# Board.net
KiCad netlist of a schematic drawn in EAGLE
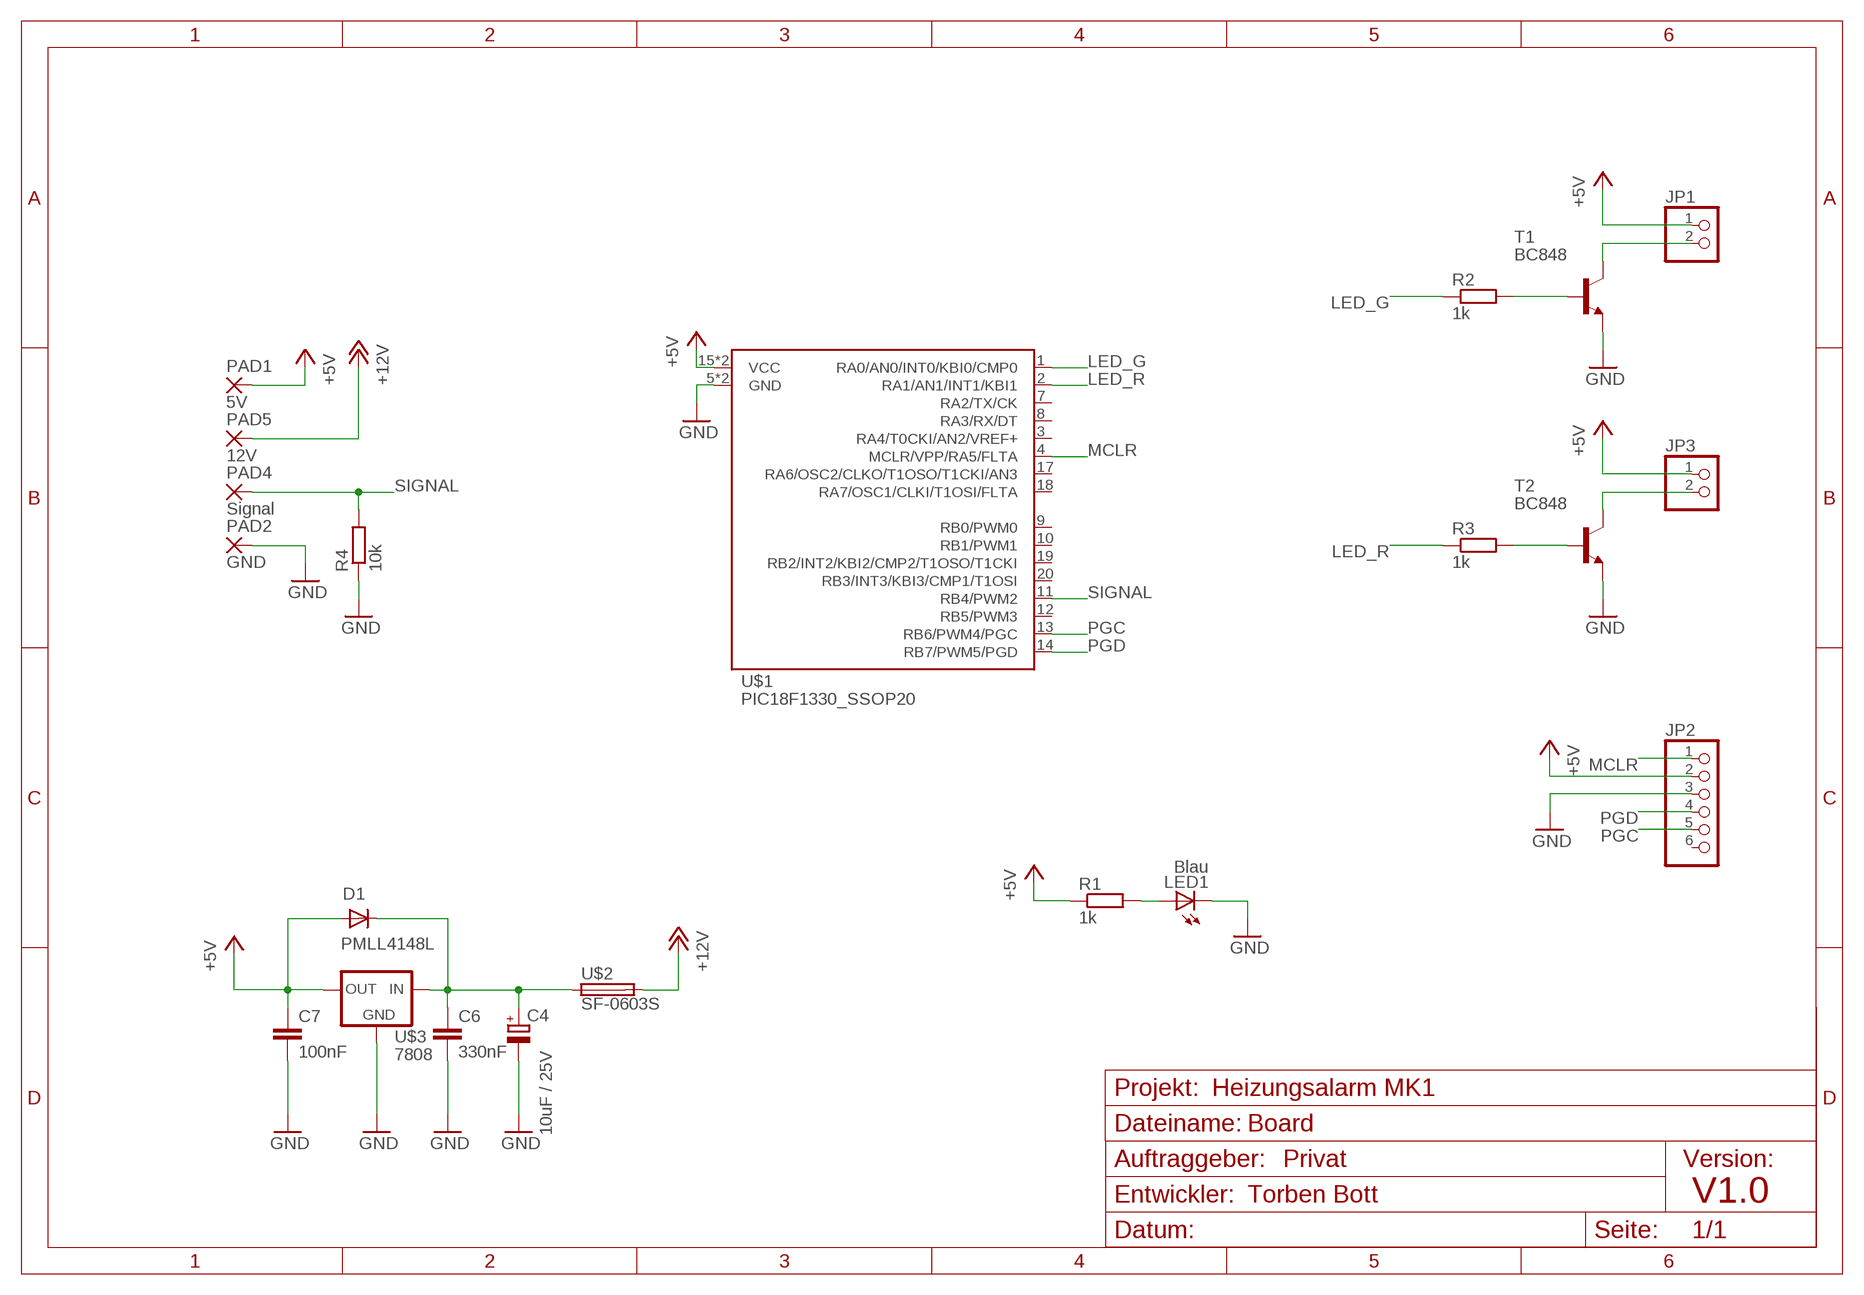
[diagram p0: schematic, sheet 1]

(export (version "E")
  (design (tool "Eeschema 10.0.6"))
  (components
    (comp (ref "C4")
      (value "10uF / 25V")
      (footprint "eagle-import:D_7343-31R")
      (libsource (lib "eagle-import") (part "CPOL-EUD/7343-31R"))
    )
    (comp (ref "C6")
      (value "330nF")
      (footprint "eagle-import:C0805")
      (libsource (lib "eagle-import") (part "C-EUC0805"))
    )
    (comp (ref "C7")
      (value "100nF")
      (footprint "eagle-import:C0805")
      (libsource (lib "eagle-import") (part "C-EUC0805"))
    )
    (comp (ref "D1")
      (value "PMLL4148L")
      (footprint "eagle-import:SOD80C")
      (libsource (lib "eagle-import") (part "PMLL4148L"))
    )
    (comp (ref "JP1")
      (value "PINHD-1X2/90")
      (footprint "eagle-import:1X02_90")
      (libsource (lib "eagle-import") (part "PINHD-1X2/90"))
    )
    (comp (ref "JP2")
      (value "PINHD-1X6")
      (footprint "eagle-import:1X06")
      (libsource (lib "eagle-import") (part "PINHD-1X6"))
    )
    (comp (ref "JP3")
      (value "PINHD-1X2/90")
      (footprint "eagle-import:1X02_90")
      (libsource (lib "eagle-import") (part "PINHD-1X2/90"))
    )
    (comp (ref "LED1")
      (value "Blau")
      (footprint "eagle-import:CHIP-LED0805")
      (libsource (lib "eagle-import") (part "LEDCHIP-LED0805"))
    )
    (comp (ref "PAD1")
      (value "5V")
      (footprint "eagle-import:5-1,8")
      (libsource (lib "eagle-import") (part "WIREPADSMD5-1,8"))
    )
    (comp (ref "PAD2")
      (value "GND")
      (footprint "eagle-import:5-1,8")
      (libsource (lib "eagle-import") (part "WIREPADSMD5-1,8"))
    )
    (comp (ref "PAD4")
      (value "Signal")
      (footprint "eagle-import:5-1,8")
      (libsource (lib "eagle-import") (part "WIREPADSMD5-1,8"))
    )
    (comp (ref "PAD5")
      (value "12V")
      (footprint "eagle-import:5-1,8")
      (libsource (lib "eagle-import") (part "WIREPADSMD5-1,8"))
    )
    (comp (ref "R1")
      (value "1k")
      (footprint "eagle-import:R0805")
      (libsource (lib "eagle-import") (part "R-EU_R0805"))
    )
    (comp (ref "R2")
      (value "1k")
      (footprint "eagle-import:R0805")
      (libsource (lib "eagle-import") (part "R-EU_R0805"))
    )
    (comp (ref "R3")
      (value "1k")
      (footprint "eagle-import:R0805")
      (libsource (lib "eagle-import") (part "R-EU_R0805"))
    )
    (comp (ref "R4")
      (value "10k")
      (footprint "eagle-import:R0805")
      (libsource (lib "eagle-import") (part "R-EU_R0805"))
    )
    (comp (ref "T1")
      (value "BC848")
      (footprint "eagle-import:SOT23")
      (libsource (lib "eagle-import") (part "BC848"))
    )
    (comp (ref "T2")
      (value "BC848")
      (footprint "eagle-import:SOT23")
      (libsource (lib "eagle-import") (part "BC848"))
    )
    (comp (ref "U$1")
      (value "PIC18F1330_SSOP20")
      (footprint "eagle-import:SSOP20")
      (libsource (lib "eagle-import") (part "PIC18F1330_SSOP20"))
    )
    (comp (ref "U$2")
      (value "SF-0603S")
      (footprint "eagle-import:R0603")
      (libsource (lib "eagle-import") (part "SF-0603S"))
    )
    (comp (ref "U$3")
      (value "7808")
      (footprint "eagle-import:SOT89")
      (libsource (lib "eagle-import") (part "78XX_(SOT89)"))
    )
  )
  (nets
    (net (code "1") (name "+5V") (class "Default")
      (node (ref "C7") (pin "1") (pinfunction "1_1") (pintype "passive"))
      (node (ref "D1") (pin "2") (pinfunction "A_2") (pintype "passive"))
      (node (ref "JP1") (pin "1") (pinfunction "1_1") (pintype "passive"))
      (node (ref "JP2") (pin "2") (pinfunction "2_2") (pintype "passive"))
      (node (ref "JP3") (pin "1") (pinfunction "1_1") (pintype "passive"))
      (node (ref "PAD1") (pin "1") (pinfunction "P_1") (pintype "passive"))
      (node (ref "R1") (pin "1") (pinfunction "1_1") (pintype "passive"))
      (node (ref "U$1") (pin "15") (pinfunction "VCC_15") (pintype "bidirectional"))
      (node (ref "U$1") (pin "16") (pinfunction "VCC_16") (pintype "bidirectional"))
      (node (ref "U$3") (pin "1") (pinfunction "IN_1") (pintype "input"))
    )
    (net (code "2") (name "+12V") (class "Default")
      (node (ref "PAD5") (pin "1") (pinfunction "P_1") (pintype "passive"))
      (node (ref "U$2") (pin "2") (pinfunction "2_2") (pintype "passive"))
    )
    (net (code "3") (name "/LED_G") (class "Default")
      (node (ref "R2") (pin "1") (pinfunction "1_1") (pintype "passive"))
      (node (ref "U$1") (pin "1") (pinfunction "RA0/AN0/INT0/KBI0/CMP0_1") (pintype "bidirectional"))
    )
    (net (code "4") (name "/LED_R") (class "Default")
      (node (ref "R3") (pin "1") (pinfunction "1_1") (pintype "passive"))
      (node (ref "U$1") (pin "2") (pinfunction "RA1/AN1/INT1/KBI1_2") (pintype "bidirectional"))
    )
    (net (code "5") (name "/MCLR") (class "Default")
      (node (ref "JP2") (pin "1") (pinfunction "1_1") (pintype "passive"))
      (node (ref "U$1") (pin "4") (pinfunction "MCLR/VPP/RA5/FLTA_4") (pintype "bidirectional"))
    )
    (net (code "6") (name "/PGC") (class "Default")
      (node (ref "JP2") (pin "5") (pinfunction "5_5") (pintype "passive"))
      (node (ref "U$1") (pin "13") (pinfunction "RB6/PWM4/PGC_13") (pintype "bidirectional"))
    )
    (net (code "7") (name "/PGD") (class "Default")
      (node (ref "JP2") (pin "4") (pinfunction "4_4") (pintype "passive"))
      (node (ref "U$1") (pin "14") (pinfunction "RB7/PWM5/PGD_14") (pintype "bidirectional"))
    )
    (net (code "8") (name "/SIGNAL") (class "Default")
      (node (ref "PAD4") (pin "1") (pinfunction "P_1") (pintype "passive"))
      (node (ref "R4") (pin "2") (pinfunction "2_2") (pintype "passive"))
      (node (ref "U$1") (pin "11") (pinfunction "RB4/PWM2_11") (pintype "bidirectional"))
    )
    (net (code "9") (name "GND") (class "Default")
      (node (ref "C4") (pin "-") (pinfunction "-_-") (pintype "passive"))
      (node (ref "C6") (pin "2") (pinfunction "2_2") (pintype "passive"))
      (node (ref "C7") (pin "2") (pinfunction "2_2") (pintype "passive"))
      (node (ref "JP2") (pin "3") (pinfunction "3_3") (pintype "passive"))
      (node (ref "LED1") (pin "C") (pinfunction "C_C") (pintype "passive"))
      (node (ref "PAD2") (pin "1") (pinfunction "P_1") (pintype "passive"))
      (node (ref "R4") (pin "1") (pinfunction "1_1") (pintype "passive"))
      (node (ref "T1") (pin "2") (pinfunction "E_2") (pintype "passive"))
      (node (ref "T2") (pin "2") (pinfunction "E_2") (pintype "passive"))
      (node (ref "U$1") (pin "5") (pinfunction "GND_5") (pintype "bidirectional"))
      (node (ref "U$1") (pin "6") (pinfunction "GND_6") (pintype "bidirectional"))
      (node (ref "U$3") (pin "2") (pinfunction "GND_2") (pintype "input"))
      (node (ref "U$3") (pin "2@1") (pinfunction "GND_2@1") (pintype "input"))
    )
    (net (code "10") (name "Net-(D1-K)") (class "Default")
      (node (ref "C4") (pin "+") (pinfunction "+_+") (pintype "passive"))
      (node (ref "C6") (pin "1") (pinfunction "1_1") (pintype "passive"))
      (node (ref "D1") (pin "1") (pinfunction "K_1") (pintype "passive"))
      (node (ref "U$2") (pin "1") (pinfunction "1_1") (pintype "passive"))
      (node (ref "U$3") (pin "3") (pinfunction "OUT_3") (pintype "passive"))
    )
    (net (code "11") (name "Net-(LED1-PadA)") (class "Default")
      (node (ref "LED1") (pin "A") (pinfunction "A_A") (pintype "passive"))
      (node (ref "R1") (pin "2") (pinfunction "2_2") (pintype "passive"))
    )
    (net (code "12") (name "Net-(T1-B)") (class "Default")
      (node (ref "R2") (pin "2") (pinfunction "2_2") (pintype "passive"))
      (node (ref "T1") (pin "1") (pinfunction "B_1") (pintype "passive"))
    )
    (net (code "13") (name "Net-(T1-C)") (class "Default")
      (node (ref "JP1") (pin "2") (pinfunction "2_2") (pintype "passive"))
      (node (ref "T1") (pin "3") (pinfunction "C_3") (pintype "passive"))
    )
    (net (code "14") (name "Net-(T2-B)") (class "Default")
      (node (ref "R3") (pin "2") (pinfunction "2_2") (pintype "passive"))
      (node (ref "T2") (pin "1") (pinfunction "B_1") (pintype "passive"))
    )
    (net (code "15") (name "Net-(T2-C)") (class "Default")
      (node (ref "JP3") (pin "2") (pinfunction "2_2") (pintype "passive"))
      (node (ref "T2") (pin "3") (pinfunction "C_3") (pintype "passive"))
    )
    (net (code "16") (name "unconnected-(JP2-Pad6)") (class "Default")
      (node (ref "JP2") (pin "6") (pinfunction "6_6") (pintype "passive"))
    )
    (net (code "17") (name "unconnected-(U$1-RA2{slash}TX{slash}CK-Pad7)") (class "Default")
      (node (ref "U$1") (pin "7") (pinfunction "RA2/TX/CK_7") (pintype "bidirectional"))
    )
    (net (code "18") (name "unconnected-(U$1-RA3{slash}RX{slash}DT-Pad8)") (class "Default")
      (node (ref "U$1") (pin "8") (pinfunction "RA3/RX/DT_8") (pintype "bidirectional"))
    )
    (net (code "19") (name "unconnected-(U$1-RA4{slash}T0CKI{slash}AN2{slash}VREF+-Pad3)") (class "Default")
      (node (ref "U$1") (pin "3") (pinfunction "RA4/T0CKI/AN2/VREF+_3") (pintype "bidirectional"))
    )
    (net (code "20") (name "unconnected-(U$1-RA6{slash}OSC2{slash}CLKO{slash}T1OSO{slash}T1CKI{slash}AN3-Pad17)") (class "Default")
      (node (ref "U$1") (pin "17") (pinfunction "RA6/OSC2/CLKO/T1OSO/T1CKI/AN3_17") (pintype "bidirectional"))
    )
    (net (code "21") (name "unconnected-(U$1-RA7{slash}OSC1{slash}CLKI{slash}T1OSI{slash}FLTA-Pad18)") (class "Default")
      (node (ref "U$1") (pin "18") (pinfunction "RA7/OSC1/CLKI/T1OSI/FLTA_18") (pintype "bidirectional"))
    )
    (net (code "22") (name "unconnected-(U$1-RB0{slash}PWM0-Pad9)") (class "Default")
      (node (ref "U$1") (pin "9") (pinfunction "RB0/PWM0_9") (pintype "bidirectional"))
    )
    (net (code "23") (name "unconnected-(U$1-RB1{slash}PWM1-Pad10)") (class "Default")
      (node (ref "U$1") (pin "10") (pinfunction "RB1/PWM1_10") (pintype "bidirectional"))
    )
    (net (code "24") (name "unconnected-(U$1-RB2{slash}INT2{slash}KBI2{slash}CMP2{slash}T1OSO{slash}T1CKI-Pad19)") (class "Default")
      (node (ref "U$1") (pin "19") (pinfunction "RB2/INT2/KBI2/CMP2/T1OSO/T1CKI_19") (pintype "bidirectional"))
    )
    (net (code "25") (name "unconnected-(U$1-RB3{slash}INT3{slash}KBI3{slash}CMP1{slash}T1OSI-Pad20)") (class "Default")
      (node (ref "U$1") (pin "20") (pinfunction "RB3/INT3/KBI3/CMP1/T1OSI_20") (pintype "bidirectional"))
    )
    (net (code "26") (name "unconnected-(U$1-RB5{slash}PWM3-Pad12)") (class "Default")
      (node (ref "U$1") (pin "12") (pinfunction "RB5/PWM3_12") (pintype "bidirectional"))
    )
  )
)
